# Button.net
KiCad netlist of a schematic drawn in EAGLE
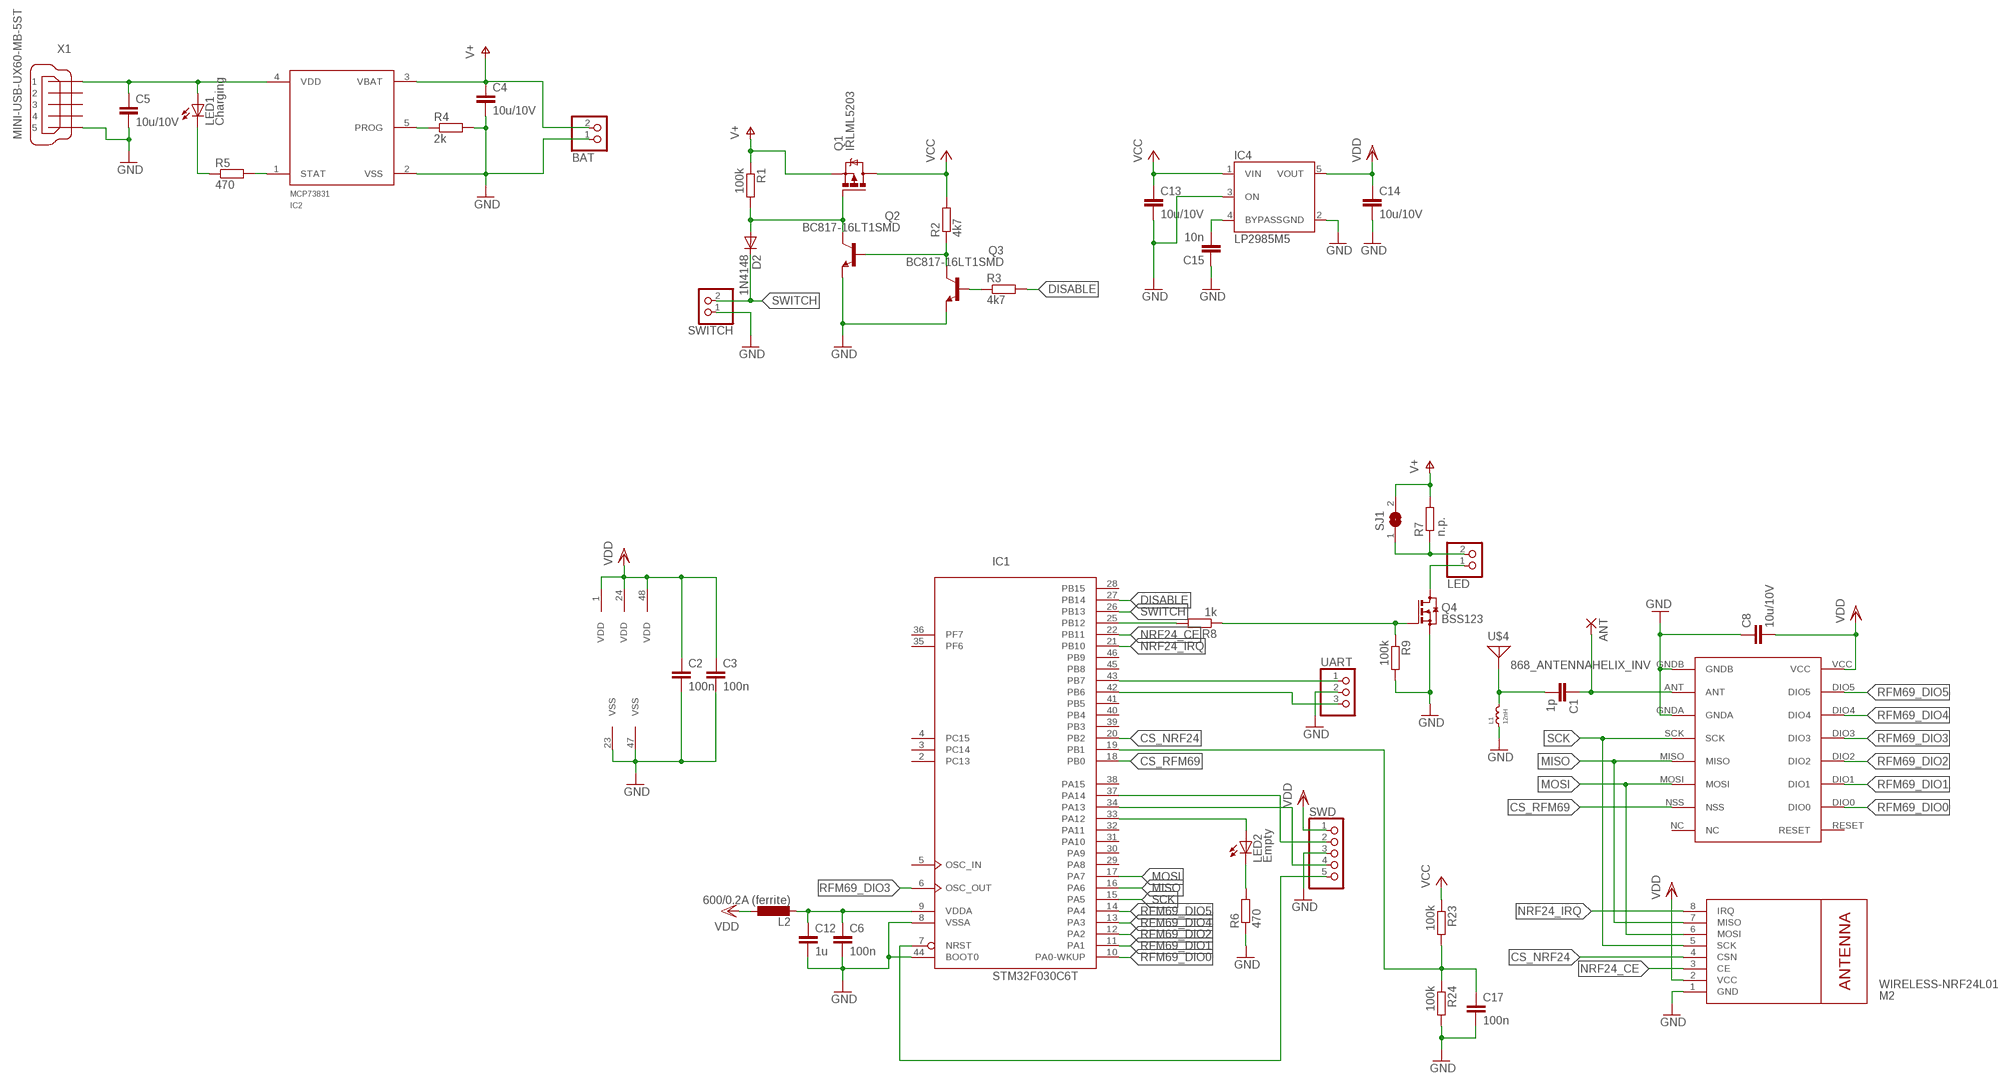
[diagram p0: schematic, sheet 1]

(export (version "E")
  (design (tool "Eeschema 10.0.6"))
  (components
    (comp (ref "ANT")
      (value "1,6/0,8")
      (footprint "eagle-import:1,6_0,8")
      (libsource (lib "eagle-import") (part "1,6/0,8"))
    )
    (comp (ref "BAT")
      (value "PINHD-1X2")
      (footprint "eagle-import:1X02")
      (libsource (lib "eagle-import") (part "PINHD-1X2"))
    )
    (comp (ref "C1")
      (value "1p")
      (footprint "eagle-import:C0603")
      (libsource (lib "eagle-import") (part "C-EUC0603"))
    )
    (comp (ref "C2")
      (value "100n")
      (footprint "eagle-import:C0603")
      (libsource (lib "eagle-import") (part "C-EUC0603"))
    )
    (comp (ref "C3")
      (value "100n")
      (footprint "eagle-import:C0603")
      (libsource (lib "eagle-import") (part "C-EUC0603"))
    )
    (comp (ref "C4")
      (value "10u/10V")
      (footprint "eagle-import:C1206")
      (libsource (lib "eagle-import") (part "C-EUC1206"))
    )
    (comp (ref "C5")
      (value "10u/10V")
      (footprint "eagle-import:C1206")
      (libsource (lib "eagle-import") (part "C-EUC1206"))
    )
    (comp (ref "C6")
      (value "100n")
      (footprint "eagle-import:C0603")
      (libsource (lib "eagle-import") (part "C-EUC0603"))
    )
    (comp (ref "C8")
      (value "10u/10V")
      (footprint "eagle-import:C1206")
      (libsource (lib "eagle-import") (part "C-EUC1206"))
    )
    (comp (ref "C12")
      (value "1u")
      (footprint "eagle-import:C0603")
      (libsource (lib "eagle-import") (part "C-EUC0603"))
    )
    (comp (ref "C13")
      (value "10u/10V")
      (footprint "eagle-import:C1206")
      (libsource (lib "eagle-import") (part "C-EUC1206"))
    )
    (comp (ref "C14")
      (value "10u/10V")
      (footprint "eagle-import:C1206")
      (libsource (lib "eagle-import") (part "C-EUC1206"))
    )
    (comp (ref "C15")
      (value "10n")
      (footprint "eagle-import:C0603")
      (libsource (lib "eagle-import") (part "C-EUC0603"))
    )
    (comp (ref "C17")
      (value "100n")
      (footprint "eagle-import:C0603")
      (libsource (lib "eagle-import") (part "C-EUC0603"))
    )
    (comp (ref "D2")
      (value "1N4148")
      (footprint "eagle-import:SOD323-W")
      (libsource (lib "eagle-import") (part "DIODE-SOD323-W"))
    )
    (comp (ref "IC1")
      (value "STM32F030C6T")
      (footprint "eagle-import:LQFP48")
      (libsource (lib "eagle-import") (part "STM32F030CT6"))
    )
    (comp (ref "IC2")
      (value "MCP73831")
      (footprint "eagle-import:SOT23-5")
      (libsource (lib "eagle-import") (part "MCP73831"))
    )
    (comp (ref "IC4")
      (value "LP2985M5")
      (footprint "eagle-import:SOT23-5")
      (libsource (lib "eagle-import") (part "LP2985M5"))
    )
    (comp (ref "L1")
      (value "12nH")
      (footprint "eagle-import:0603")
      (libsource (lib "eagle-import") (part "RF-INDUCTOR.0603"))
    )
    (comp (ref "L2")
      (value "600/0.2A (ferrite)")
      (footprint "eagle-import:L2012C")
      (libsource (lib "eagle-import") (part "L-EUL2012C"))
    )
    (comp (ref "LED")
      (value "PINHD-1X2")
      (footprint "eagle-import:1X02")
      (libsource (lib "eagle-import") (part "PINHD-1X2"))
    )
    (comp (ref "LED1")
      (value "Charging")
      (footprint "eagle-import:CHIPLED_0603")
      (libsource (lib "eagle-import") (part "LEDCHIPLED_0603"))
    )
    (comp (ref "LED2")
      (value "Empty")
      (footprint "eagle-import:CHIPLED_0603")
      (libsource (lib "eagle-import") (part "LEDCHIPLED_0603"))
    )
    (comp (ref "M2")
      (value "WIRELESS-NRF24L01")
      (footprint "eagle-import:WIRELESS-NRF24L01")
      (libsource (lib "eagle-import") (part "WIRELESS-NRF24L01"))
    )
    (comp (ref "Q1")
      (value "IRLML5203")
      (footprint "eagle-import:MICRO3")
      (libsource (lib "eagle-import") (part "IRLML5203"))
    )
    (comp (ref "Q2")
      (value "BC817-16LT1SMD")
      (footprint "eagle-import:SOT23-BEC")
      (libsource (lib "eagle-import") (part "BC817SMD-16LT1"))
    )
    (comp (ref "Q3")
      (value "BC817-16LT1SMD")
      (footprint "eagle-import:SOT23-BEC")
      (libsource (lib "eagle-import") (part "BC817SMD-16LT1"))
    )
    (comp (ref "Q4")
      (value "BSS123")
      (footprint "eagle-import:SOT23")
      (libsource (lib "eagle-import") (part "BSS123"))
    )
    (comp (ref "R1")
      (value "100k")
      (footprint "eagle-import:R0603")
      (libsource (lib "eagle-import") (part "R-EU_R0603"))
    )
    (comp (ref "R2")
      (value "4k7")
      (footprint "eagle-import:R0603")
      (libsource (lib "eagle-import") (part "R-EU_R0603"))
    )
    (comp (ref "R3")
      (value "4k7")
      (footprint "eagle-import:R0603")
      (libsource (lib "eagle-import") (part "R-EU_R0603"))
    )
    (comp (ref "R4")
      (value "2k")
      (footprint "eagle-import:R0603")
      (libsource (lib "eagle-import") (part "R-EU_R0603"))
    )
    (comp (ref "R5")
      (value "470")
      (footprint "eagle-import:R0603")
      (libsource (lib "eagle-import") (part "R-EU_R0603"))
    )
    (comp (ref "R6")
      (value "470")
      (footprint "eagle-import:R0603")
      (libsource (lib "eagle-import") (part "R-EU_R0603"))
    )
    (comp (ref "R7")
      (value "n.p.")
      (footprint "eagle-import:R1206")
      (libsource (lib "eagle-import") (part "R-EU_R1206"))
    )
    (comp (ref "R8")
      (value "1k")
      (footprint "eagle-import:R0603")
      (libsource (lib "eagle-import") (part "R-EU_R0603"))
    )
    (comp (ref "R9")
      (value "100k")
      (footprint "eagle-import:R0603")
      (libsource (lib "eagle-import") (part "R-EU_R0603"))
    )
    (comp (ref "R23")
      (value "100k")
      (footprint "eagle-import:R0603")
      (libsource (lib "eagle-import") (part "R-EU_R0603"))
    )
    (comp (ref "R24")
      (value "100k")
      (footprint "eagle-import:R0603")
      (libsource (lib "eagle-import") (part "R-EU_R0603"))
    )
    (comp (ref "SJ1") (value "SJ") (footprint "eagle-import:SJ") (libsource (lib "eagle-import") (part "SJ")))
    (comp (ref "SWD")
      (value "PINHD-1X5")
      (footprint "eagle-import:1X05")
      (libsource (lib "eagle-import") (part "PINHD-1X5"))
    )
    (comp (ref "SWITCH")
      (value "PINHD-1X2")
      (footprint "eagle-import:1X02")
      (libsource (lib "eagle-import") (part "PINHD-1X2"))
    )
    (comp (ref "U$1")
      (value "RFM69HW")
      (footprint "eagle-import:RFM")
      (libsource (lib "eagle-import") (part "RFM69HW"))
    )
    (comp (ref "U$4")
      (value "868_ANTENNAHELIX_INV")
      (footprint "eagle-import:HELIX_868_INV")
      (libsource (lib "eagle-import") (part "868_ANTENNAHELIX_INV"))
    )
    (comp (ref "UART")
      (value "PINHD-1X3")
      (footprint "eagle-import:1X03")
      (libsource (lib "eagle-import") (part "PINHD-1X3"))
    )
    (comp (ref "X1")
      (value "MINI-USB-UX60-MB-5ST")
      (footprint "eagle-import:UX60-MB-5ST")
      (libsource (lib "eagle-import") (part "MINI-USB-UX60-MB-5ST"))
    )
  )
  (nets
    (net (code "1") (name "CS_NRF24") (class "Default")
      (node (ref "IC1") (pin "20") (pinfunction "PB2_20") (pintype "bidirectional"))
      (node (ref "M2") (pin "4") (pinfunction "CSN_4") (pintype "bidirectional"))
    )
    (net (code "2") (name "CS_RFM69") (class "Default")
      (node (ref "IC1") (pin "18") (pinfunction "PB0_18") (pintype "bidirectional"))
      (node (ref "U$1") (pin "NSS") (pinfunction "NSS_NSS") (pintype "bidirectional"))
    )
    (net (code "3") (name "DISABLE") (class "Default")
      (node (ref "IC1") (pin "27") (pinfunction "PB14_27") (pintype "bidirectional"))
      (node (ref "R3") (pin "2") (pinfunction "2_2") (pintype "passive"))
    )
    (net (code "4") (name "GND") (class "Default")
      (node (ref "BAT") (pin "1") (pinfunction "1_1") (pintype "passive"))
      (node (ref "C12") (pin "2") (pinfunction "2_2") (pintype "passive"))
      (node (ref "C13") (pin "2") (pinfunction "2_2") (pintype "passive"))
      (node (ref "C14") (pin "2") (pinfunction "2_2") (pintype "passive"))
      (node (ref "C15") (pin "1") (pinfunction "1_1") (pintype "passive"))
      (node (ref "C17") (pin "2") (pinfunction "2_2") (pintype "passive"))
      (node (ref "C2") (pin "2") (pinfunction "2_2") (pintype "passive"))
      (node (ref "C3") (pin "2") (pinfunction "2_2") (pintype "passive"))
      (node (ref "C4") (pin "2") (pinfunction "2_2") (pintype "passive"))
      (node (ref "C5") (pin "2") (pinfunction "2_2") (pintype "passive"))
      (node (ref "C6") (pin "2") (pinfunction "2_2") (pintype "passive"))
      (node (ref "C8") (pin "1") (pinfunction "1_1") (pintype "passive"))
      (node (ref "IC1") (pin "23") (pinfunction "VSS_23") (pintype "power_in"))
      (node (ref "IC1") (pin "44") (pinfunction "BOOT0_44") (pintype "input"))
      (node (ref "IC1") (pin "47") (pinfunction "VSS_47") (pintype "power_in"))
      (node (ref "IC1") (pin "8") (pinfunction "VSSA_8") (pintype "power_in"))
      (node (ref "IC2") (pin "2") (pinfunction "VSS_2") (pintype "bidirectional"))
      (node (ref "IC4") (pin "2") (pinfunction "GND_2") (pintype "power_in"))
      (node (ref "IC4") (pin "3") (pinfunction "ON_3") (pintype "input"))
      (node (ref "L1") (pin "1") (pinfunction "1_1") (pintype "passive"))
      (node (ref "M2") (pin "1") (pinfunction "GND_1") (pintype "power_in"))
      (node (ref "Q2") (pin "E") (pinfunction "E_E") (pintype "passive"))
      (node (ref "Q3") (pin "E") (pinfunction "E_E") (pintype "passive"))
      (node (ref "Q4") (pin "2") (pinfunction "S_2") (pintype "passive"))
      (node (ref "R24") (pin "2") (pinfunction "2_2") (pintype "passive"))
      (node (ref "R4") (pin "2") (pinfunction "2_2") (pintype "passive"))
      (node (ref "R6") (pin "1") (pinfunction "1_1") (pintype "passive"))
      (node (ref "R9") (pin "2") (pinfunction "2_2") (pintype "passive"))
      (node (ref "SWD") (pin "3") (pinfunction "3_3") (pintype "passive"))
      (node (ref "SWITCH") (pin "1") (pinfunction "1_1") (pintype "passive"))
      (node (ref "U$1") (pin "GNDA") (pinfunction "GNDA_GNDA") (pintype "bidirectional"))
      (node (ref "U$1") (pin "GNDB") (pinfunction "GNDB_GNDB") (pintype "bidirectional"))
      (node (ref "UART") (pin "2") (pinfunction "2_2") (pintype "passive"))
      (node (ref "X1") (pin "5") (pinfunction "5_5") (pintype "input"))
    )
    (net (code "5") (name "MISO") (class "Default")
      (node (ref "IC1") (pin "16") (pinfunction "PA6_16") (pintype "bidirectional"))
      (node (ref "M2") (pin "7") (pinfunction "MISO_7") (pintype "bidirectional"))
      (node (ref "U$1") (pin "MISO") (pinfunction "MISO_MISO") (pintype "bidirectional"))
    )
    (net (code "6") (name "MOSI") (class "Default")
      (node (ref "IC1") (pin "17") (pinfunction "PA7_17") (pintype "bidirectional"))
      (node (ref "M2") (pin "6") (pinfunction "MOSI_6") (pintype "bidirectional"))
      (node (ref "U$1") (pin "MOSI") (pinfunction "MOSI_MOSI") (pintype "bidirectional"))
    )
    (net (code "7") (name "NRF24_CE") (class "Default")
      (node (ref "IC1") (pin "22") (pinfunction "PB11_22") (pintype "bidirectional"))
      (node (ref "M2") (pin "3") (pinfunction "CE_3") (pintype "bidirectional"))
    )
    (net (code "8") (name "NRF24_IRQ") (class "Default")
      (node (ref "IC1") (pin "21") (pinfunction "PB10_21") (pintype "bidirectional"))
      (node (ref "M2") (pin "8") (pinfunction "IRQ_8") (pintype "bidirectional"))
    )
    (net (code "9") (name "Net-(ANT-P)") (class "Default")
      (node (ref "ANT") (pin "1") (pinfunction "P_1") (pintype "passive"))
      (node (ref "C1") (pin "1") (pinfunction "1_1") (pintype "passive"))
      (node (ref "U$1") (pin "ANT") (pinfunction "ANT_ANT") (pintype "bidirectional"))
    )
    (net (code "10") (name "Net-(C1-Pad2)") (class "Default")
      (node (ref "C1") (pin "2") (pinfunction "2_2") (pintype "passive"))
      (node (ref "L1") (pin "2") (pinfunction "2_2") (pintype "passive"))
      (node (ref "U$4") (pin "ANT") (pinfunction "1_ANT") (pintype "output"))
      (node (ref "U$4") (pin "P$10") (pinfunction "1_P$10") (pintype "output"))
      (node (ref "U$4") (pin "P$11") (pinfunction "1_P$11") (pintype "output"))
      (node (ref "U$4") (pin "P$12") (pinfunction "1_P$12") (pintype "output"))
      (node (ref "U$4") (pin "P$13") (pinfunction "1_P$13") (pintype "output"))
      (node (ref "U$4") (pin "P$14") (pinfunction "1_P$14") (pintype "output"))
      (node (ref "U$4") (pin "P$15") (pinfunction "1_P$15") (pintype "output"))
      (node (ref "U$4") (pin "P$16") (pinfunction "1_P$16") (pintype "output"))
      (node (ref "U$4") (pin "P$17") (pinfunction "1_P$17") (pintype "output"))
      (node (ref "U$4") (pin "P$18") (pinfunction "1_P$18") (pintype "output"))
      (node (ref "U$4") (pin "P$19") (pinfunction "1_P$19") (pintype "output"))
      (node (ref "U$4") (pin "P$2") (pinfunction "1_P$2") (pintype "output"))
      (node (ref "U$4") (pin "P$20") (pinfunction "1_P$20") (pintype "output"))
      (node (ref "U$4") (pin "P$3") (pinfunction "1_P$3") (pintype "output"))
      (node (ref "U$4") (pin "P$4") (pinfunction "1_P$4") (pintype "output"))
      (node (ref "U$4") (pin "P$5") (pinfunction "1_P$5") (pintype "output"))
      (node (ref "U$4") (pin "P$6") (pinfunction "1_P$6") (pintype "output"))
      (node (ref "U$4") (pin "P$7") (pinfunction "1_P$7") (pintype "output"))
      (node (ref "U$4") (pin "P$8") (pinfunction "1_P$8") (pintype "output"))
      (node (ref "U$4") (pin "P$9") (pinfunction "1_P$9") (pintype "output"))
    )
    (net (code "11") (name "Net-(IC1A-NRST)") (class "Default")
      (node (ref "IC1") (pin "7") (pinfunction "NRST_7") (pintype "bidirectional"))
      (node (ref "SWD") (pin "5") (pinfunction "5_5") (pintype "passive"))
    )
    (net (code "12") (name "Net-(IC1A-PA12)") (class "Default")
      (node (ref "IC1") (pin "33") (pinfunction "PA12_33") (pintype "bidirectional"))
      (node (ref "LED2") (pin "A") (pinfunction "A_A") (pintype "passive"))
    )
    (net (code "13") (name "Net-(IC1A-PA13)") (class "Default")
      (node (ref "IC1") (pin "34") (pinfunction "PA13_34") (pintype "bidirectional"))
      (node (ref "SWD") (pin "4") (pinfunction "4_4") (pintype "passive"))
    )
    (net (code "14") (name "Net-(IC1A-PA14)") (class "Default")
      (node (ref "IC1") (pin "37") (pinfunction "PA14_37") (pintype "bidirectional"))
      (node (ref "SWD") (pin "2") (pinfunction "2_2") (pintype "passive"))
    )
    (net (code "15") (name "Net-(IC1A-PB1)") (class "Default")
      (node (ref "C17") (pin "1") (pinfunction "1_1") (pintype "passive"))
      (node (ref "IC1") (pin "19") (pinfunction "PB1_19") (pintype "bidirectional"))
      (node (ref "R23") (pin "2") (pinfunction "2_2") (pintype "passive"))
      (node (ref "R24") (pin "1") (pinfunction "1_1") (pintype "passive"))
    )
    (net (code "16") (name "Net-(IC1A-PB6)") (class "Default")
      (node (ref "IC1") (pin "42") (pinfunction "PB6_42") (pintype "bidirectional"))
      (node (ref "UART") (pin "3") (pinfunction "3_3") (pintype "passive"))
    )
    (net (code "17") (name "Net-(IC1A-PB7)") (class "Default")
      (node (ref "IC1") (pin "43") (pinfunction "PB7_43") (pintype "bidirectional"))
      (node (ref "UART") (pin "1") (pinfunction "1_1") (pintype "passive"))
    )
    (net (code "18") (name "Net-(IC1A-PB12)") (class "Default")
      (node (ref "IC1") (pin "25") (pinfunction "PB12_25") (pintype "bidirectional"))
      (node (ref "R8") (pin "2") (pinfunction "2_2") (pintype "passive"))
    )
    (net (code "19") (name "Net-(IC1A-VDDA)") (class "Default")
      (node (ref "C12") (pin "1") (pinfunction "1_1") (pintype "passive"))
      (node (ref "C6") (pin "1") (pinfunction "1_1") (pintype "passive"))
      (node (ref "IC1") (pin "9") (pinfunction "VDDA_9") (pintype "power_in"))
      (node (ref "L2") (pin "2") (pinfunction "2_2") (pintype "passive"))
    )
    (net (code "20") (name "Net-(IC2-PROG)") (class "Default")
      (node (ref "IC2") (pin "5") (pinfunction "PROG_5") (pintype "bidirectional"))
      (node (ref "R4") (pin "1") (pinfunction "1_1") (pintype "passive"))
    )
    (net (code "21") (name "Net-(IC2-STAT)") (class "Default")
      (node (ref "IC2") (pin "1") (pinfunction "STAT_1") (pintype "bidirectional"))
      (node (ref "R5") (pin "2") (pinfunction "2_2") (pintype "passive"))
    )
    (net (code "22") (name "Net-(IC2-VDD)") (class "Default")
      (node (ref "C5") (pin "1") (pinfunction "1_1") (pintype "passive"))
      (node (ref "IC2") (pin "4") (pinfunction "VDD_4") (pintype "bidirectional"))
      (node (ref "LED1") (pin "A") (pinfunction "A_A") (pintype "passive"))
      (node (ref "X1") (pin "1") (pinfunction "1_1") (pintype "input"))
    )
    (net (code "23") (name "Net-(IC4-BYPASS)") (class "Default")
      (node (ref "C15") (pin "2") (pinfunction "2_2") (pintype "passive"))
      (node (ref "IC4") (pin "4") (pinfunction "BYPASS_4") (pintype "passive"))
    )
    (net (code "24") (name "Net-(LED-Pad2)") (class "Default")
      (node (ref "LED") (pin "2") (pinfunction "2_2") (pintype "passive"))
      (node (ref "R7") (pin "1") (pinfunction "1_1") (pintype "passive"))
      (node (ref "SJ1") (pin "1") (pinfunction "1_1") (pintype "passive"))
    )
    (net (code "25") (name "Net-(LED1-PadC)") (class "Default")
      (node (ref "LED1") (pin "C") (pinfunction "C_C") (pintype "passive"))
      (node (ref "R5") (pin "1") (pinfunction "1_1") (pintype "passive"))
    )
    (net (code "26") (name "Net-(LED2-PadC)") (class "Default")
      (node (ref "LED2") (pin "C") (pinfunction "C_C") (pintype "passive"))
      (node (ref "R6") (pin "2") (pinfunction "2_2") (pintype "passive"))
    )
    (net (code "27") (name "Net-(Q1-G)") (class "Default")
      (node (ref "D2") (pin "A") (pinfunction "A_A") (pintype "passive"))
      (node (ref "Q1") (pin "1") (pinfunction "G_1") (pintype "passive"))
      (node (ref "Q2") (pin "C") (pinfunction "C_C") (pintype "passive"))
      (node (ref "R1") (pin "2") (pinfunction "2_2") (pintype "passive"))
    )
    (net (code "28") (name "Net-(Q2-PadB)") (class "Default")
      (node (ref "Q2") (pin "B") (pinfunction "B_B") (pintype "passive"))
      (node (ref "Q3") (pin "C") (pinfunction "C_C") (pintype "passive"))
      (node (ref "R2") (pin "1") (pinfunction "1_1") (pintype "passive"))
    )
    (net (code "29") (name "Net-(Q3-PadB)") (class "Default")
      (node (ref "Q3") (pin "B") (pinfunction "B_B") (pintype "passive"))
      (node (ref "R3") (pin "1") (pinfunction "1_1") (pintype "passive"))
    )
    (net (code "30") (name "Net-(Q4-D)") (class "Default")
      (node (ref "LED") (pin "1") (pinfunction "1_1") (pintype "passive"))
      (node (ref "Q4") (pin "3") (pinfunction "D_3") (pintype "passive"))
    )
    (net (code "31") (name "Net-(Q4-G)") (class "Default")
      (node (ref "Q4") (pin "1") (pinfunction "G_1") (pintype "passive"))
      (node (ref "R8") (pin "1") (pinfunction "1_1") (pintype "passive"))
      (node (ref "R9") (pin "1") (pinfunction "1_1") (pintype "passive"))
    )
    (net (code "32") (name "RFM69_DIO0") (class "Default")
      (node (ref "IC1") (pin "10") (pinfunction "PA0-WKUP_10") (pintype "bidirectional"))
      (node (ref "U$1") (pin "DIO0") (pinfunction "DIO0_DIO0") (pintype "bidirectional"))
    )
    (net (code "33") (name "RFM69_DIO1") (class "Default")
      (node (ref "IC1") (pin "11") (pinfunction "PA1_11") (pintype "bidirectional"))
      (node (ref "U$1") (pin "DIO1") (pinfunction "DIO1_DIO1") (pintype "bidirectional"))
    )
    (net (code "34") (name "RFM69_DIO2") (class "Default")
      (node (ref "IC1") (pin "12") (pinfunction "PA2_12") (pintype "bidirectional"))
      (node (ref "U$1") (pin "DIO2") (pinfunction "DIO2_DIO2") (pintype "bidirectional"))
    )
    (net (code "35") (name "RFM69_DIO3") (class "Default")
      (node (ref "IC1") (pin "6") (pinfunction "OSC_OUT_6") (pintype "bidirectional"))
      (node (ref "U$1") (pin "DIO3") (pinfunction "DIO3_DIO3") (pintype "bidirectional"))
    )
    (net (code "36") (name "RFM69_DIO4") (class "Default")
      (node (ref "IC1") (pin "13") (pinfunction "PA3_13") (pintype "bidirectional"))
      (node (ref "U$1") (pin "DIO4") (pinfunction "DIO4_DIO4") (pintype "bidirectional"))
    )
    (net (code "37") (name "RFM69_DIO5") (class "Default")
      (node (ref "IC1") (pin "14") (pinfunction "PA4_14") (pintype "bidirectional"))
      (node (ref "U$1") (pin "DIO5") (pinfunction "DIO5_DIO5") (pintype "bidirectional"))
    )
    (net (code "38") (name "SCK") (class "Default")
      (node (ref "IC1") (pin "15") (pinfunction "PA5_15") (pintype "bidirectional"))
      (node (ref "M2") (pin "5") (pinfunction "SCK_5") (pintype "bidirectional"))
      (node (ref "U$1") (pin "SCK") (pinfunction "SCK_SCK") (pintype "bidirectional"))
    )
    (net (code "39") (name "SWITCH") (class "Default")
      (node (ref "D2") (pin "C") (pinfunction "C_C") (pintype "passive"))
      (node (ref "IC1") (pin "26") (pinfunction "PB13_26") (pintype "bidirectional"))
      (node (ref "SWITCH") (pin "2") (pinfunction "2_2") (pintype "passive"))
    )
    (net (code "40") (name "V+") (class "Default")
      (node (ref "BAT") (pin "2") (pinfunction "2_2") (pintype "passive"))
      (node (ref "C4") (pin "1") (pinfunction "1_1") (pintype "passive"))
      (node (ref "IC2") (pin "3") (pinfunction "VBAT_3") (pintype "bidirectional"))
      (node (ref "Q1") (pin "2") (pinfunction "S_2") (pintype "passive"))
      (node (ref "R1") (pin "1") (pinfunction "1_1") (pintype "passive"))
      (node (ref "R7") (pin "2") (pinfunction "2_2") (pintype "passive"))
      (node (ref "SJ1") (pin "2") (pinfunction "2_2") (pintype "passive"))
    )
    (net (code "41") (name "VCC") (class "Default")
      (node (ref "C13") (pin "1") (pinfunction "1_1") (pintype "passive"))
      (node (ref "IC4") (pin "1") (pinfunction "VIN_1") (pintype "power_in"))
      (node (ref "Q1") (pin "3") (pinfunction "D_3") (pintype "passive"))
      (node (ref "R2") (pin "2") (pinfunction "2_2") (pintype "passive"))
      (node (ref "R23") (pin "1") (pinfunction "1_1") (pintype "passive"))
    )
    (net (code "42") (name "VDD") (class "Default")
      (node (ref "C14") (pin "1") (pinfunction "1_1") (pintype "passive"))
      (node (ref "C2") (pin "1") (pinfunction "1_1") (pintype "passive"))
      (node (ref "C3") (pin "1") (pinfunction "1_1") (pintype "passive"))
      (node (ref "C8") (pin "2") (pinfunction "2_2") (pintype "passive"))
      (node (ref "IC1") (pin "1") (pinfunction "VDD_1") (pintype "power_in"))
      (node (ref "IC1") (pin "24") (pinfunction "VDD_24") (pintype "power_in"))
      (node (ref "IC1") (pin "48") (pinfunction "VDD_48") (pintype "power_in"))
      (node (ref "IC4") (pin "5") (pinfunction "VOUT_5") (pintype "output"))
      (node (ref "L2") (pin "1") (pinfunction "1_1") (pintype "passive"))
      (node (ref "M2") (pin "2") (pinfunction "VCC_2") (pintype "power_in"))
      (node (ref "SWD") (pin "1") (pinfunction "1_1") (pintype "passive"))
      (node (ref "U$1") (pin "VCC") (pinfunction "VCC_VCC") (pintype "bidirectional"))
    )
    (net (code "43") (name "unconnected-(IC1A-OSC_IN-Pad5)") (class "Default")
      (node (ref "IC1") (pin "5") (pinfunction "OSC_IN_5") (pintype "bidirectional"))
    )
    (net (code "44") (name "unconnected-(IC1A-PA8-Pad29)") (class "Default")
      (node (ref "IC1") (pin "29") (pinfunction "PA8_29") (pintype "bidirectional"))
    )
    (net (code "45") (name "unconnected-(IC1A-PA9-Pad30)") (class "Default")
      (node (ref "IC1") (pin "30") (pinfunction "PA9_30") (pintype "bidirectional"))
    )
    (net (code "46") (name "unconnected-(IC1A-PA10-Pad31)") (class "Default")
      (node (ref "IC1") (pin "31") (pinfunction "PA10_31") (pintype "bidirectional"))
    )
    (net (code "47") (name "unconnected-(IC1A-PA11-Pad32)") (class "Default")
      (node (ref "IC1") (pin "32") (pinfunction "PA11_32") (pintype "bidirectional"))
    )
    (net (code "48") (name "unconnected-(IC1A-PA15-Pad38)") (class "Default")
      (node (ref "IC1") (pin "38") (pinfunction "PA15_38") (pintype "bidirectional"))
    )
    (net (code "49") (name "unconnected-(IC1A-PB3-Pad39)") (class "Default")
      (node (ref "IC1") (pin "39") (pinfunction "PB3_39") (pintype "bidirectional"))
    )
    (net (code "50") (name "unconnected-(IC1A-PB4-Pad40)") (class "Default")
      (node (ref "IC1") (pin "40") (pinfunction "PB4_40") (pintype "bidirectional"))
    )
    (net (code "51") (name "unconnected-(IC1A-PB5-Pad41)") (class "Default")
      (node (ref "IC1") (pin "41") (pinfunction "PB5_41") (pintype "bidirectional"))
    )
    (net (code "52") (name "unconnected-(IC1A-PB8-Pad45)") (class "Default")
      (node (ref "IC1") (pin "45") (pinfunction "PB8_45") (pintype "bidirectional"))
    )
    (net (code "53") (name "unconnected-(IC1A-PB9-Pad46)") (class "Default")
      (node (ref "IC1") (pin "46") (pinfunction "PB9_46") (pintype "bidirectional"))
    )
    (net (code "54") (name "unconnected-(IC1A-PB15-Pad28)") (class "Default")
      (node (ref "IC1") (pin "28") (pinfunction "PB15_28") (pintype "bidirectional"))
    )
    (net (code "55") (name "unconnected-(IC1A-PC13-Pad2)") (class "Default")
      (node (ref "IC1") (pin "2") (pinfunction "PC13_2") (pintype "bidirectional"))
    )
    (net (code "56") (name "unconnected-(IC1A-PC14-Pad3)") (class "Default")
      (node (ref "IC1") (pin "3") (pinfunction "PC14_3") (pintype "bidirectional"))
    )
    (net (code "57") (name "unconnected-(IC1A-PC15-Pad4)") (class "Default")
      (node (ref "IC1") (pin "4") (pinfunction "PC15_4") (pintype "bidirectional"))
    )
    (net (code "58") (name "unconnected-(IC1A-PF6-Pad35)") (class "Default")
      (node (ref "IC1") (pin "35") (pinfunction "PF6_35") (pintype "bidirectional"))
    )
    (net (code "59") (name "unconnected-(IC1A-PF7-Pad36)") (class "Default")
      (node (ref "IC1") (pin "36") (pinfunction "PF7_36") (pintype "bidirectional"))
    )
    (net (code "60") (name "unconnected-(U$1-PadNC)") (class "Default")
      (node (ref "U$1") (pin "NC") (pinfunction "NC_NC") (pintype "bidirectional"))
    )
    (net (code "61") (name "unconnected-(U$1-PadRESET)") (class "Default")
      (node (ref "U$1") (pin "RESET") (pinfunction "RESET_RESET") (pintype "bidirectional"))
    )
    (net (code "62") (name "unconnected-(X1-Pad2)") (class "Default")
      (node (ref "X1") (pin "2") (pinfunction "2_2") (pintype "input"))
    )
    (net (code "63") (name "unconnected-(X1-Pad3)") (class "Default")
      (node (ref "X1") (pin "3") (pinfunction "3_3") (pintype "input"))
    )
    (net (code "64") (name "unconnected-(X1-Pad4)") (class "Default")
      (node (ref "X1") (pin "4") (pinfunction "4_4") (pintype "input"))
    )
  )
)
